# cable_v2.net
KiCad netlist of a schematic drawn in EAGLE
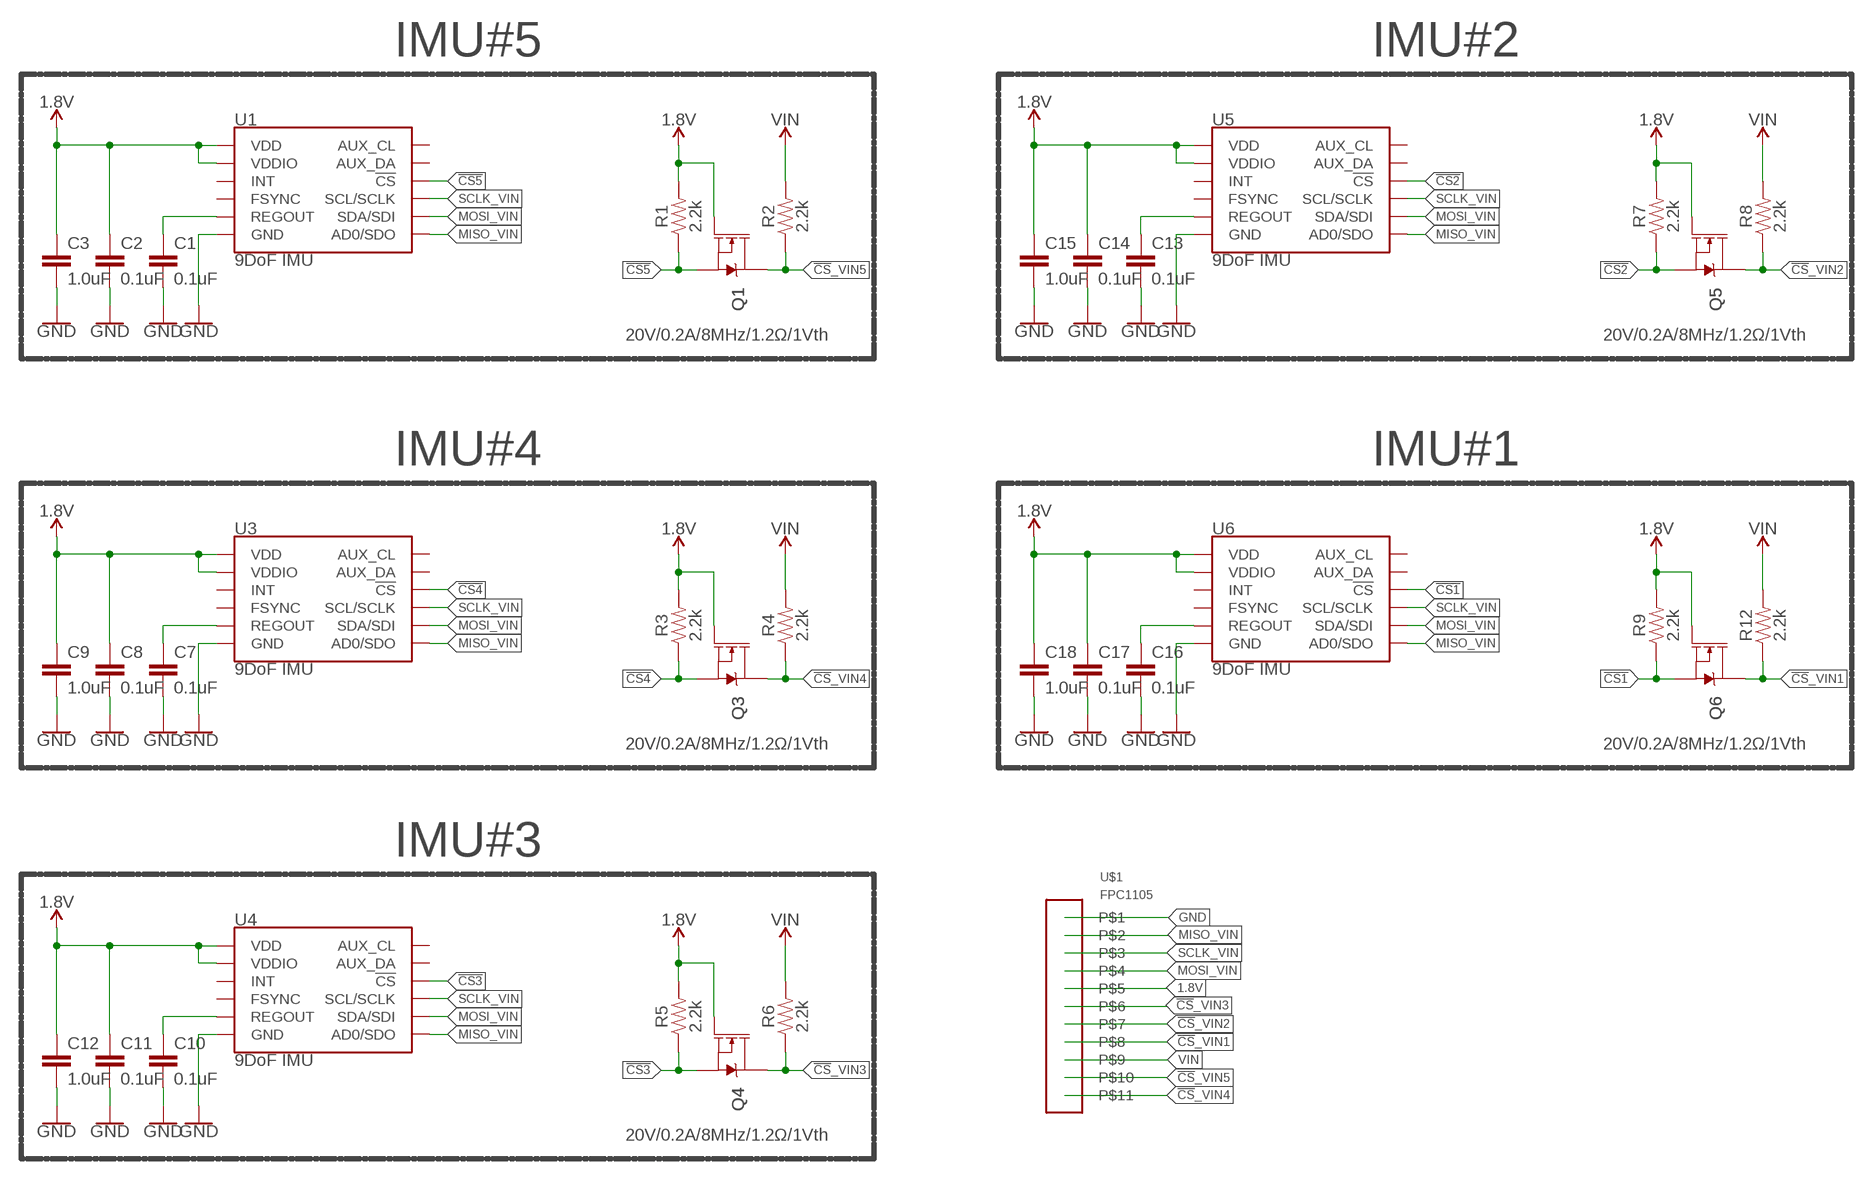
[diagram p0: schematic, sheet 1]

(export (version "E")
  (design (tool "Eeschema 10.0.6"))
  (components
    (comp (ref "C1")
      (value "0.1uF")
      (footprint "eagle-import:C0402")
      (libsource (lib "eagle-import") (part "C-EUC0402"))
    )
    (comp (ref "C2")
      (value "0.1uF")
      (footprint "eagle-import:C0402")
      (libsource (lib "eagle-import") (part "C-EUC0402"))
    )
    (comp (ref "C3")
      (value "1.0uF")
      (footprint "eagle-import:C0402")
      (libsource (lib "eagle-import") (part "C-EUC0402"))
    )
    (comp (ref "C7")
      (value "0.1uF")
      (footprint "eagle-import:C0402")
      (libsource (lib "eagle-import") (part "C-EUC0402"))
    )
    (comp (ref "C8")
      (value "0.1uF")
      (footprint "eagle-import:C0402")
      (libsource (lib "eagle-import") (part "C-EUC0402"))
    )
    (comp (ref "C9")
      (value "1.0uF")
      (footprint "eagle-import:C0402")
      (libsource (lib "eagle-import") (part "C-EUC0402"))
    )
    (comp (ref "C10")
      (value "0.1uF")
      (footprint "eagle-import:C0402")
      (libsource (lib "eagle-import") (part "C-EUC0402"))
    )
    (comp (ref "C11")
      (value "0.1uF")
      (footprint "eagle-import:C0402")
      (libsource (lib "eagle-import") (part "C-EUC0402"))
    )
    (comp (ref "C12")
      (value "1.0uF")
      (footprint "eagle-import:C0402")
      (libsource (lib "eagle-import") (part "C-EUC0402"))
    )
    (comp (ref "C13")
      (value "0.1uF")
      (footprint "eagle-import:C0402")
      (libsource (lib "eagle-import") (part "C-EUC0402"))
    )
    (comp (ref "C14")
      (value "0.1uF")
      (footprint "eagle-import:C0402")
      (libsource (lib "eagle-import") (part "C-EUC0402"))
    )
    (comp (ref "C15")
      (value "1.0uF")
      (footprint "eagle-import:C0402")
      (libsource (lib "eagle-import") (part "C-EUC0402"))
    )
    (comp (ref "C16")
      (value "0.1uF")
      (footprint "eagle-import:C0402")
      (libsource (lib "eagle-import") (part "C-EUC0402"))
    )
    (comp (ref "C17")
      (value "0.1uF")
      (footprint "eagle-import:C0402")
      (libsource (lib "eagle-import") (part "C-EUC0402"))
    )
    (comp (ref "C18")
      (value "1.0uF")
      (footprint "eagle-import:C0402")
      (libsource (lib "eagle-import") (part "C-EUC0402"))
    )
    (comp (ref "Q1")
      (value "20V/0.2A/8MHz/1.2Ω/1Vth")
      (footprint "eagle-import:SOT-416FL")
      (libsource (lib "eagle-import") (part "MOSFET-NCH-RE1C002UN"))
    )
    (comp (ref "Q3")
      (value "20V/0.2A/8MHz/1.2Ω/1Vth")
      (footprint "eagle-import:SOT-416FL")
      (libsource (lib "eagle-import") (part "MOSFET-NCH-RE1C002UN"))
    )
    (comp (ref "Q4")
      (value "20V/0.2A/8MHz/1.2Ω/1Vth")
      (footprint "eagle-import:SOT-416FL")
      (libsource (lib "eagle-import") (part "MOSFET-NCH-RE1C002UN"))
    )
    (comp (ref "Q5")
      (value "20V/0.2A/8MHz/1.2Ω/1Vth")
      (footprint "eagle-import:SOT-416FL")
      (libsource (lib "eagle-import") (part "MOSFET-NCH-RE1C002UN"))
    )
    (comp (ref "Q6")
      (value "20V/0.2A/8MHz/1.2Ω/1Vth")
      (footprint "eagle-import:SOT-416FL")
      (libsource (lib "eagle-import") (part "MOSFET-NCH-RE1C002UN"))
    )
    (comp (ref "R1")
      (value "2.2k")
      (footprint "eagle-import:0402-TIGHT")
      (libsource (lib "eagle-import") (part "2.2KOHM-0402T-1/16W-1%"))
    )
    (comp (ref "R2")
      (value "2.2k")
      (footprint "eagle-import:0402-TIGHT")
      (libsource (lib "eagle-import") (part "2.2KOHM-0402T-1/16W-1%"))
    )
    (comp (ref "R3")
      (value "2.2k")
      (footprint "eagle-import:0402-TIGHT")
      (libsource (lib "eagle-import") (part "2.2KOHM-0402T-1/16W-1%"))
    )
    (comp (ref "R4")
      (value "2.2k")
      (footprint "eagle-import:0402-TIGHT")
      (libsource (lib "eagle-import") (part "2.2KOHM-0402T-1/16W-1%"))
    )
    (comp (ref "R5")
      (value "2.2k")
      (footprint "eagle-import:0402-TIGHT")
      (libsource (lib "eagle-import") (part "2.2KOHM-0402T-1/16W-1%"))
    )
    (comp (ref "R6")
      (value "2.2k")
      (footprint "eagle-import:0402-TIGHT")
      (libsource (lib "eagle-import") (part "2.2KOHM-0402T-1/16W-1%"))
    )
    (comp (ref "R7")
      (value "2.2k")
      (footprint "eagle-import:0402-TIGHT")
      (libsource (lib "eagle-import") (part "2.2KOHM-0402T-1/16W-1%"))
    )
    (comp (ref "R8")
      (value "2.2k")
      (footprint "eagle-import:0402-TIGHT")
      (libsource (lib "eagle-import") (part "2.2KOHM-0402T-1/16W-1%"))
    )
    (comp (ref "R9")
      (value "2.2k")
      (footprint "eagle-import:0402-TIGHT")
      (libsource (lib "eagle-import") (part "2.2KOHM-0402T-1/16W-1%"))
    )
    (comp (ref "R12")
      (value "2.2k")
      (footprint "eagle-import:0402-TIGHT")
      (libsource (lib "eagle-import") (part "2.2KOHM-0402T-1/16W-1%"))
    )
    (comp (ref "U$1")
      (value "FPC1105")
      (footprint "eagle-import:FPC1105")
      (libsource (lib "eagle-import") (part "FPC1105"))
    )
    (comp (ref "U1")
      (value "9DoF IMU")
      (footprint "eagle-import:QFN24-3X3")
      (libsource (lib "eagle-import") (part "ICM-20948"))
    )
    (comp (ref "U3")
      (value "9DoF IMU")
      (footprint "eagle-import:QFN24-3X3")
      (libsource (lib "eagle-import") (part "ICM-20948"))
    )
    (comp (ref "U4")
      (value "9DoF IMU")
      (footprint "eagle-import:QFN24-3X3")
      (libsource (lib "eagle-import") (part "ICM-20948"))
    )
    (comp (ref "U5")
      (value "9DoF IMU")
      (footprint "eagle-import:QFN24-3X3")
      (libsource (lib "eagle-import") (part "ICM-20948"))
    )
    (comp (ref "U6")
      (value "9DoF IMU")
      (footprint "eagle-import:QFN24-3X3")
      (libsource (lib "eagle-import") (part "ICM-20948"))
    )
  )
  (nets
    (net (code "1") (name "/~{CS1}") (class "Default")
      (node (ref "Q6") (pin "2") (pinfunction "S_2") (pintype "bidirectional"))
      (node (ref "R9") (pin "1") (pinfunction "1_1") (pintype "passive"))
      (node (ref "U6") (pin "22") (pinfunction "~{CS}_22") (pintype "bidirectional"))
    )
    (net (code "2") (name "/~{CS2}") (class "Default")
      (node (ref "Q5") (pin "2") (pinfunction "S_2") (pintype "bidirectional"))
      (node (ref "R7") (pin "1") (pinfunction "1_1") (pintype "passive"))
      (node (ref "U5") (pin "22") (pinfunction "~{CS}_22") (pintype "bidirectional"))
    )
    (net (code "3") (name "/~{CS3}") (class "Default")
      (node (ref "Q4") (pin "2") (pinfunction "S_2") (pintype "bidirectional"))
      (node (ref "R5") (pin "1") (pinfunction "1_1") (pintype "passive"))
      (node (ref "U4") (pin "22") (pinfunction "~{CS}_22") (pintype "bidirectional"))
    )
    (net (code "4") (name "/~{CS4}") (class "Default")
      (node (ref "Q3") (pin "2") (pinfunction "S_2") (pintype "bidirectional"))
      (node (ref "R3") (pin "1") (pinfunction "1_1") (pintype "passive"))
      (node (ref "U3") (pin "22") (pinfunction "~{CS}_22") (pintype "bidirectional"))
    )
    (net (code "5") (name "/~{CS5}") (class "Default")
      (node (ref "Q1") (pin "2") (pinfunction "S_2") (pintype "bidirectional"))
      (node (ref "R1") (pin "1") (pinfunction "1_1") (pintype "passive"))
      (node (ref "U1") (pin "22") (pinfunction "~{CS}_22") (pintype "bidirectional"))
    )
    (net (code "6") (name "/~{CS}_VIN1") (class "Default")
      (node (ref "Q6") (pin "3") (pinfunction "D_3") (pintype "bidirectional"))
      (node (ref "R12") (pin "1") (pinfunction "1_1") (pintype "passive"))
      (node (ref "U$1") (pin "P$8") (pinfunction "P$8_P$8") (pintype "bidirectional"))
    )
    (net (code "7") (name "/~{CS}_VIN2") (class "Default")
      (node (ref "Q5") (pin "3") (pinfunction "D_3") (pintype "bidirectional"))
      (node (ref "R8") (pin "1") (pinfunction "1_1") (pintype "passive"))
      (node (ref "U$1") (pin "P$7") (pinfunction "P$7_P$7") (pintype "bidirectional"))
    )
    (net (code "8") (name "/~{CS}_VIN3") (class "Default")
      (node (ref "Q4") (pin "3") (pinfunction "D_3") (pintype "bidirectional"))
      (node (ref "R6") (pin "1") (pinfunction "1_1") (pintype "passive"))
      (node (ref "U$1") (pin "P$6") (pinfunction "P$6_P$6") (pintype "bidirectional"))
    )
    (net (code "9") (name "/~{CS}_VIN4") (class "Default")
      (node (ref "Q3") (pin "3") (pinfunction "D_3") (pintype "bidirectional"))
      (node (ref "R4") (pin "1") (pinfunction "1_1") (pintype "passive"))
      (node (ref "U$1") (pin "P$11") (pinfunction "P$11_P$11") (pintype "bidirectional"))
    )
    (net (code "10") (name "/~{CS}_VIN5") (class "Default")
      (node (ref "Q1") (pin "3") (pinfunction "D_3") (pintype "bidirectional"))
      (node (ref "R2") (pin "1") (pinfunction "1_1") (pintype "passive"))
      (node (ref "U$1") (pin "P$10") (pinfunction "P$10_P$10") (pintype "bidirectional"))
    )
    (net (code "11") (name "1.8V") (class "Default")
      (node (ref "C11") (pin "1") (pinfunction "1_1") (pintype "passive"))
      (node (ref "C12") (pin "1") (pinfunction "1_1") (pintype "passive"))
      (node (ref "C14") (pin "1") (pinfunction "1_1") (pintype "passive"))
      (node (ref "C15") (pin "1") (pinfunction "1_1") (pintype "passive"))
      (node (ref "C17") (pin "1") (pinfunction "1_1") (pintype "passive"))
      (node (ref "C18") (pin "1") (pinfunction "1_1") (pintype "passive"))
      (node (ref "C2") (pin "1") (pinfunction "1_1") (pintype "passive"))
      (node (ref "C3") (pin "1") (pinfunction "1_1") (pintype "passive"))
      (node (ref "C8") (pin "1") (pinfunction "1_1") (pintype "passive"))
      (node (ref "C9") (pin "1") (pinfunction "1_1") (pintype "passive"))
      (node (ref "Q1") (pin "1") (pinfunction "G_1") (pintype "bidirectional"))
      (node (ref "Q3") (pin "1") (pinfunction "G_1") (pintype "bidirectional"))
      (node (ref "Q4") (pin "1") (pinfunction "G_1") (pintype "bidirectional"))
      (node (ref "Q5") (pin "1") (pinfunction "G_1") (pintype "bidirectional"))
      (node (ref "Q6") (pin "1") (pinfunction "G_1") (pintype "bidirectional"))
      (node (ref "R1") (pin "2") (pinfunction "2_2") (pintype "passive"))
      (node (ref "R3") (pin "2") (pinfunction "2_2") (pintype "passive"))
      (node (ref "R5") (pin "2") (pinfunction "2_2") (pintype "passive"))
      (node (ref "R7") (pin "2") (pinfunction "2_2") (pintype "passive"))
      (node (ref "R9") (pin "2") (pinfunction "2_2") (pintype "passive"))
      (node (ref "U$1") (pin "P$5") (pinfunction "P$5_P$5") (pintype "bidirectional"))
      (node (ref "U1") (pin "13") (pinfunction "VDD_13") (pintype "bidirectional"))
      (node (ref "U1") (pin "8") (pinfunction "VDDIO_8") (pintype "bidirectional"))
      (node (ref "U3") (pin "13") (pinfunction "VDD_13") (pintype "bidirectional"))
      (node (ref "U3") (pin "8") (pinfunction "VDDIO_8") (pintype "bidirectional"))
      (node (ref "U4") (pin "13") (pinfunction "VDD_13") (pintype "bidirectional"))
      (node (ref "U4") (pin "8") (pinfunction "VDDIO_8") (pintype "bidirectional"))
      (node (ref "U5") (pin "13") (pinfunction "VDD_13") (pintype "bidirectional"))
      (node (ref "U5") (pin "8") (pinfunction "VDDIO_8") (pintype "bidirectional"))
      (node (ref "U6") (pin "13") (pinfunction "VDD_13") (pintype "bidirectional"))
      (node (ref "U6") (pin "8") (pinfunction "VDDIO_8") (pintype "bidirectional"))
    )
    (net (code "12") (name "GND") (class "Default")
      (node (ref "C1") (pin "2") (pinfunction "2_2") (pintype "passive"))
      (node (ref "C10") (pin "2") (pinfunction "2_2") (pintype "passive"))
      (node (ref "C11") (pin "2") (pinfunction "2_2") (pintype "passive"))
      (node (ref "C12") (pin "2") (pinfunction "2_2") (pintype "passive"))
      (node (ref "C13") (pin "2") (pinfunction "2_2") (pintype "passive"))
      (node (ref "C14") (pin "2") (pinfunction "2_2") (pintype "passive"))
      (node (ref "C15") (pin "2") (pinfunction "2_2") (pintype "passive"))
      (node (ref "C16") (pin "2") (pinfunction "2_2") (pintype "passive"))
      (node (ref "C17") (pin "2") (pinfunction "2_2") (pintype "passive"))
      (node (ref "C18") (pin "2") (pinfunction "2_2") (pintype "passive"))
      (node (ref "C2") (pin "2") (pinfunction "2_2") (pintype "passive"))
      (node (ref "C3") (pin "2") (pinfunction "2_2") (pintype "passive"))
      (node (ref "C7") (pin "2") (pinfunction "2_2") (pintype "passive"))
      (node (ref "C8") (pin "2") (pinfunction "2_2") (pintype "passive"))
      (node (ref "C9") (pin "2") (pinfunction "2_2") (pintype "passive"))
      (node (ref "U$1") (pin "P$1") (pinfunction "P$1_P$1") (pintype "bidirectional"))
      (node (ref "U1") (pin "18") (pinfunction "GND_18") (pintype "bidirectional"))
      (node (ref "U1") (pin "20") (pinfunction "GND_20") (pintype "bidirectional"))
      (node (ref "U3") (pin "18") (pinfunction "GND_18") (pintype "bidirectional"))
      (node (ref "U3") (pin "20") (pinfunction "GND_20") (pintype "bidirectional"))
      (node (ref "U4") (pin "18") (pinfunction "GND_18") (pintype "bidirectional"))
      (node (ref "U4") (pin "20") (pinfunction "GND_20") (pintype "bidirectional"))
      (node (ref "U5") (pin "18") (pinfunction "GND_18") (pintype "bidirectional"))
      (node (ref "U5") (pin "20") (pinfunction "GND_20") (pintype "bidirectional"))
      (node (ref "U6") (pin "18") (pinfunction "GND_18") (pintype "bidirectional"))
      (node (ref "U6") (pin "20") (pinfunction "GND_20") (pintype "bidirectional"))
    )
    (net (code "13") (name "MISO_VIN") (class "Default")
      (node (ref "U$1") (pin "P$2") (pinfunction "P$2_P$2") (pintype "bidirectional"))
      (node (ref "U1") (pin "9") (pinfunction "AD0/SDO_9") (pintype "bidirectional"))
      (node (ref "U3") (pin "9") (pinfunction "AD0/SDO_9") (pintype "bidirectional"))
      (node (ref "U4") (pin "9") (pinfunction "AD0/SDO_9") (pintype "bidirectional"))
      (node (ref "U5") (pin "9") (pinfunction "AD0/SDO_9") (pintype "bidirectional"))
      (node (ref "U6") (pin "9") (pinfunction "AD0/SDO_9") (pintype "bidirectional"))
    )
    (net (code "14") (name "MOSI_VIN") (class "Default")
      (node (ref "U$1") (pin "P$4") (pinfunction "P$4_P$4") (pintype "bidirectional"))
      (node (ref "U1") (pin "24") (pinfunction "SDA/SDI_24") (pintype "bidirectional"))
      (node (ref "U3") (pin "24") (pinfunction "SDA/SDI_24") (pintype "bidirectional"))
      (node (ref "U4") (pin "24") (pinfunction "SDA/SDI_24") (pintype "bidirectional"))
      (node (ref "U5") (pin "24") (pinfunction "SDA/SDI_24") (pintype "bidirectional"))
      (node (ref "U6") (pin "24") (pinfunction "SDA/SDI_24") (pintype "bidirectional"))
    )
    (net (code "15") (name "Net-(U1-REGOUT)") (class "Default")
      (node (ref "C1") (pin "1") (pinfunction "1_1") (pintype "passive"))
      (node (ref "U1") (pin "10") (pinfunction "REGOUT_10") (pintype "bidirectional"))
    )
    (net (code "16") (name "Net-(U3-REGOUT)") (class "Default")
      (node (ref "C7") (pin "1") (pinfunction "1_1") (pintype "passive"))
      (node (ref "U3") (pin "10") (pinfunction "REGOUT_10") (pintype "bidirectional"))
    )
    (net (code "17") (name "Net-(U4-REGOUT)") (class "Default")
      (node (ref "C10") (pin "1") (pinfunction "1_1") (pintype "passive"))
      (node (ref "U4") (pin "10") (pinfunction "REGOUT_10") (pintype "bidirectional"))
    )
    (net (code "18") (name "Net-(U5-REGOUT)") (class "Default")
      (node (ref "C13") (pin "1") (pinfunction "1_1") (pintype "passive"))
      (node (ref "U5") (pin "10") (pinfunction "REGOUT_10") (pintype "bidirectional"))
    )
    (net (code "19") (name "Net-(U6-REGOUT)") (class "Default")
      (node (ref "C16") (pin "1") (pinfunction "1_1") (pintype "passive"))
      (node (ref "U6") (pin "10") (pinfunction "REGOUT_10") (pintype "bidirectional"))
    )
    (net (code "20") (name "SCLK_VIN") (class "Default")
      (node (ref "U$1") (pin "P$3") (pinfunction "P$3_P$3") (pintype "bidirectional"))
      (node (ref "U1") (pin "23") (pinfunction "SCL/SCLK_23") (pintype "bidirectional"))
      (node (ref "U3") (pin "23") (pinfunction "SCL/SCLK_23") (pintype "bidirectional"))
      (node (ref "U4") (pin "23") (pinfunction "SCL/SCLK_23") (pintype "bidirectional"))
      (node (ref "U5") (pin "23") (pinfunction "SCL/SCLK_23") (pintype "bidirectional"))
      (node (ref "U6") (pin "23") (pinfunction "SCL/SCLK_23") (pintype "bidirectional"))
    )
    (net (code "21") (name "VIN") (class "Default")
      (node (ref "R12") (pin "2") (pinfunction "2_2") (pintype "passive"))
      (node (ref "R2") (pin "2") (pinfunction "2_2") (pintype "passive"))
      (node (ref "R4") (pin "2") (pinfunction "2_2") (pintype "passive"))
      (node (ref "R6") (pin "2") (pinfunction "2_2") (pintype "passive"))
      (node (ref "R8") (pin "2") (pinfunction "2_2") (pintype "passive"))
      (node (ref "U$1") (pin "P$9") (pinfunction "P$9_P$9") (pintype "bidirectional"))
    )
    (net (code "22") (name "unconnected-(U1-AUX_CL-Pad7)") (class "Default")
      (node (ref "U1") (pin "7") (pinfunction "AUX_CL_7") (pintype "bidirectional"))
    )
    (net (code "23") (name "unconnected-(U1-AUX_DA-Pad21)") (class "Default")
      (node (ref "U1") (pin "21") (pinfunction "AUX_DA_21") (pintype "bidirectional"))
    )
    (net (code "24") (name "unconnected-(U1-FSYNC-Pad11)") (class "Default")
      (node (ref "U1") (pin "11") (pinfunction "FSYNC_11") (pintype "bidirectional"))
    )
    (net (code "25") (name "unconnected-(U1-INT-Pad12)") (class "Default")
      (node (ref "U1") (pin "12") (pinfunction "INT_12") (pintype "bidirectional"))
    )
    (net (code "26") (name "unconnected-(U3-AUX_CL-Pad7)") (class "Default")
      (node (ref "U3") (pin "7") (pinfunction "AUX_CL_7") (pintype "bidirectional"))
    )
    (net (code "27") (name "unconnected-(U3-AUX_DA-Pad21)") (class "Default")
      (node (ref "U3") (pin "21") (pinfunction "AUX_DA_21") (pintype "bidirectional"))
    )
    (net (code "28") (name "unconnected-(U3-FSYNC-Pad11)") (class "Default")
      (node (ref "U3") (pin "11") (pinfunction "FSYNC_11") (pintype "bidirectional"))
    )
    (net (code "29") (name "unconnected-(U3-INT-Pad12)") (class "Default")
      (node (ref "U3") (pin "12") (pinfunction "INT_12") (pintype "bidirectional"))
    )
    (net (code "30") (name "unconnected-(U4-AUX_CL-Pad7)") (class "Default")
      (node (ref "U4") (pin "7") (pinfunction "AUX_CL_7") (pintype "bidirectional"))
    )
    (net (code "31") (name "unconnected-(U4-AUX_DA-Pad21)") (class "Default")
      (node (ref "U4") (pin "21") (pinfunction "AUX_DA_21") (pintype "bidirectional"))
    )
    (net (code "32") (name "unconnected-(U4-FSYNC-Pad11)") (class "Default")
      (node (ref "U4") (pin "11") (pinfunction "FSYNC_11") (pintype "bidirectional"))
    )
    (net (code "33") (name "unconnected-(U4-INT-Pad12)") (class "Default")
      (node (ref "U4") (pin "12") (pinfunction "INT_12") (pintype "bidirectional"))
    )
    (net (code "34") (name "unconnected-(U5-AUX_CL-Pad7)") (class "Default")
      (node (ref "U5") (pin "7") (pinfunction "AUX_CL_7") (pintype "bidirectional"))
    )
    (net (code "35") (name "unconnected-(U5-AUX_DA-Pad21)") (class "Default")
      (node (ref "U5") (pin "21") (pinfunction "AUX_DA_21") (pintype "bidirectional"))
    )
    (net (code "36") (name "unconnected-(U5-FSYNC-Pad11)") (class "Default")
      (node (ref "U5") (pin "11") (pinfunction "FSYNC_11") (pintype "bidirectional"))
    )
    (net (code "37") (name "unconnected-(U5-INT-Pad12)") (class "Default")
      (node (ref "U5") (pin "12") (pinfunction "INT_12") (pintype "bidirectional"))
    )
    (net (code "38") (name "unconnected-(U6-AUX_CL-Pad7)") (class "Default")
      (node (ref "U6") (pin "7") (pinfunction "AUX_CL_7") (pintype "bidirectional"))
    )
    (net (code "39") (name "unconnected-(U6-AUX_DA-Pad21)") (class "Default")
      (node (ref "U6") (pin "21") (pinfunction "AUX_DA_21") (pintype "bidirectional"))
    )
    (net (code "40") (name "unconnected-(U6-FSYNC-Pad11)") (class "Default")
      (node (ref "U6") (pin "11") (pinfunction "FSYNC_11") (pintype "bidirectional"))
    )
    (net (code "41") (name "unconnected-(U6-INT-Pad12)") (class "Default")
      (node (ref "U6") (pin "12") (pinfunction "INT_12") (pintype "bidirectional"))
    )
  )
)
